# Cellphone-Detector-LM358.net
KiCad netlist of a schematic drawn in EAGLE
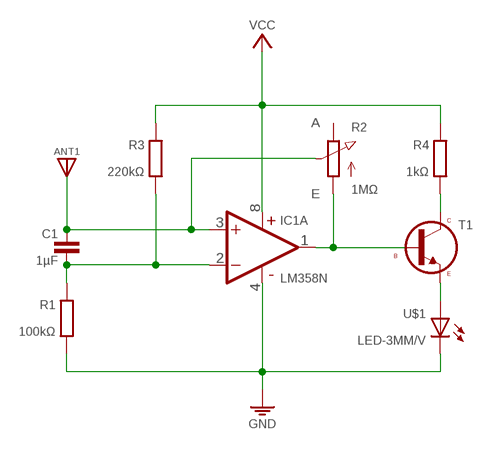
[diagram p0: schematic, sheet 1]

(export (version "E")
  (design (tool "Eeschema 10.0.6"))
  (components
    (comp (ref "ANT1")
      (value "ANT")
      (footprint "eagle-import:SPAD")
      (libsource (lib "eagle-import") (part "ANT"))
    )
    (comp (ref "C1")
      (value "1µF")
      (footprint "eagle-import:C025-024X044")
      (libsource (lib "eagle-import") (part "C025-024X044"))
    )
    (comp (ref "IC1")
      (value "LM358N")
      (footprint "eagle-import:DIL08")
      (libsource (lib "eagle-import") (part "LM358N"))
    )
    (comp (ref "R1")
      (value "100kΩ")
      (footprint "eagle-import:0202_7-V")
      (libsource (lib "eagle-import") (part "R0202/7-V"))
    )
    (comp (ref "R2")
      (value "1MΩ")
      (footprint "eagle-import:POT-V")
      (libsource (lib "eagle-import") (part "POT-V"))
    )
    (comp (ref "R3")
      (value "220kΩ")
      (footprint "eagle-import:0204_10-V")
      (libsource (lib "eagle-import") (part "R0204/10-V"))
    )
    (comp (ref "R4")
      (value "1kΩ")
      (footprint "eagle-import:0204_10-V")
      (libsource (lib "eagle-import") (part "R0204/10-V"))
    )
    (comp (ref "S1")
      (value "VCC_GNDPWR-R")
      (footprint "eagle-import:PWR-R")
      (libsource (lib "eagle-import") (part "VCC_GNDPWR-R"))
    )
    (comp (ref "T1")
      (value "BC547")
      (footprint "eagle-import:TO92")
      (libsource (lib "eagle-import") (part "BC547"))
    )
    (comp (ref "U$1")
      (value "LED-3MM/V")
      (footprint "eagle-import:LED_3MM_V")
      (libsource (lib "eagle-import") (part "LED-3MM/V"))
    )
  )
  (nets
    (net (code "1") (name "Net-(IC1A-+IN)") (class "Default")
      (node (ref "ANT1") (pin "1") (pinfunction "1_1") (pintype "output"))
      (node (ref "C1") (pin "1") (pinfunction "1_1") (pintype "passive"))
      (node (ref "IC1") (pin "3") (pinfunction "+IN_3") (pintype "input"))
      (node (ref "R2") (pin "S") (pinfunction "S_S") (pintype "passive"))
    )
    (net (code "2") (name "Net-(IC1A--IN)") (class "Default")
      (node (ref "C1") (pin "2") (pinfunction "2_2") (pintype "passive"))
      (node (ref "IC1") (pin "2") (pinfunction "-IN_2") (pintype "input"))
      (node (ref "R1") (pin "1") (pinfunction "2_1") (pintype "passive"))
      (node (ref "R3") (pin "2") (pinfunction "1_2") (pintype "passive"))
    )
    (net (code "3") (name "Net-(IC1A-OUT)") (class "Default")
      (node (ref "IC1") (pin "1") (pinfunction "OUT_1") (pintype "output"))
      (node (ref "R2") (pin "A") (pinfunction "A_A") (pintype "passive"))
      (node (ref "T1") (pin "2") (pinfunction "B_2") (pintype "passive"))
    )
    (net (code "4") (name "Net-(IC1C-V+)") (class "Default")
      (node (ref "IC1") (pin "8") (pinfunction "V+_8") (pintype "power_in"))
      (node (ref "R3") (pin "1") (pinfunction "2_1") (pintype "passive"))
      (node (ref "R4") (pin "1") (pinfunction "2_1") (pintype "passive"))
      (node (ref "S1") (pin "2") (pinfunction "VCC_2") (pintype "power_in"))
    )
    (net (code "5") (name "Net-(IC1C-V-)") (class "Default")
      (node (ref "IC1") (pin "4") (pinfunction "V-_4") (pintype "power_in"))
      (node (ref "R1") (pin "2") (pinfunction "1_2") (pintype "passive"))
      (node (ref "S1") (pin "1") (pinfunction "GND_1") (pintype "power_in"))
      (node (ref "U$1") (pin "K") (pinfunction "C_K") (pintype "passive"))
    )
    (net (code "6") (name "Net-(R4-1)") (class "Default")
      (node (ref "R4") (pin "2") (pinfunction "1_2") (pintype "passive"))
      (node (ref "T1") (pin "1") (pinfunction "C_1") (pintype "passive"))
    )
    (net (code "7") (name "Net-(T1-E)") (class "Default")
      (node (ref "T1") (pin "3") (pinfunction "E_3") (pintype "passive"))
      (node (ref "U$1") (pin "A") (pinfunction "A_A") (pintype "passive"))
    )
    (net (code "8") (name "unconnected-(R2-PadE)") (class "Default")
      (node (ref "R2") (pin "E") (pinfunction "E_E") (pintype "passive"))
    )
  )
)
